# Analog_Signal_Conditioner_V2.net
KiCad netlist of a schematic drawn in Altium Designer
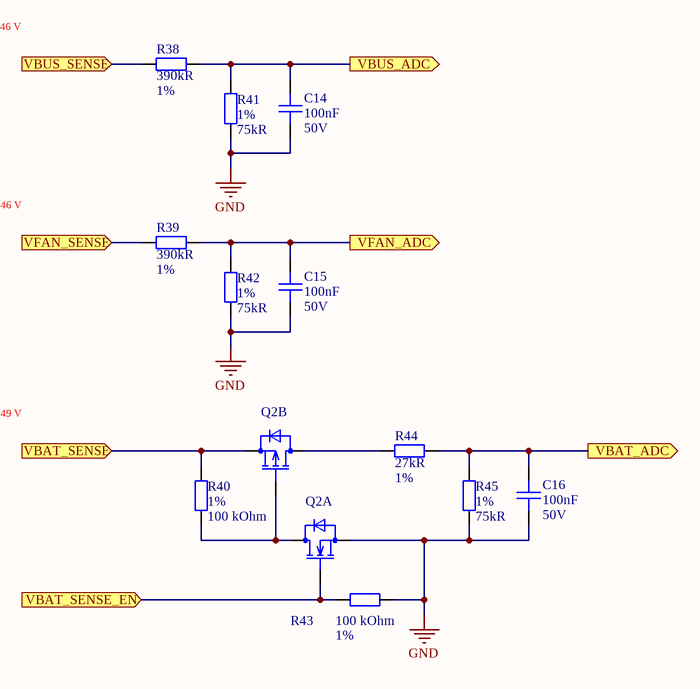
[diagram p0: Analog_Signal_Conditioner_V2.SchDoc]

(export (version "E")
  (design (tool "Eeschema 10.0.6"))
  (components
    (comp (ref "C14")
      (value "CAP CER 0.1UF 50V X7R 0402")
      (footprint "C0402")
      (description "0.1µF ±10% 50V Ceramic Capacitor X7R 0402 (1005 Metric)")
      (fields
        (field (name "MANUFACTURER PART NUMBER") "CGA2B3X7R1H104K050BB")
        (field (name "MANUFACTURER") "TDK")
        (field (name "CAPACITANCE") "100nF")
        (field (name "VOLTAGE") "50V")
      )
      (libsource (lib "capacitors_smd") (part "CAP CER 0.1UF 50V X7R 0402"))
    )
    (comp (ref "C15")
      (value "CAP CER 0.1UF 50V X7R 0402")
      (footprint "C0402")
      (description "0.1µF ±10% 50V Ceramic Capacitor X7R 0402 (1005 Metric)")
      (fields
        (field (name "MANUFACTURER PART NUMBER") "CGA2B3X7R1H104K050BB")
        (field (name "MANUFACTURER") "TDK")
        (field (name "CAPACITANCE") "100nF")
        (field (name "VOLTAGE") "50V")
      )
      (libsource (lib "capacitors_smd") (part "CAP CER 0.1UF 50V X7R 0402"))
    )
    (comp (ref "C16")
      (value "CAP CER 0.1UF 50V X7R 0402")
      (footprint "C0402")
      (description "0.1µF ±10% 50V Ceramic Capacitor X7R 0402 (1005 Metric)")
      (fields
        (field (name "MANUFACTURER PART NUMBER") "CGA2B3X7R1H104K050BB")
        (field (name "MANUFACTURER") "TDK")
        (field (name "CAPACITANCE") "100nF")
        (field (name "VOLTAGE") "50V")
      )
      (libsource (lib "capacitors_smd") (part "CAP CER 0.1UF 50V X7R 0402"))
    )
    (comp (ref "Q2")
      (value "EM6M2T2R")
      (footprint "SON_400UV-7_DIO")
      (description "Mosfet Array N and P-Channel 20V 200mA 150mW Surface Mount EMT6")
      (fields (field (name "MANUFACTURER") "Rohm"))
      (libsource (lib "mosfets") (part "ARRAY MOSFET N/P-CH 20V 0.2A EMT6"))
    )
    (comp (ref "R38")
      (value "RES SMD 390K OHM 1% 1/16W 0402")
      (footprint "R0402")
      (description "390 kOhms ±1% 0.063W, 1/16W Chip Resistor 0402 (1005 Metric) Moisture Resistant Thick Film")
      (fields
        (field (name "MANUFACTURER") "Yageo")
        (field (name "MANUFACTURER PART NUMBER") "RC0402FR-07390KL")
        (field (name "RESISTANCE") "390kR")
        (field (name "TOLERANCE") "1%")
      )
      (libsource (lib "resistors_smd") (part "RES SMD 390K OHM 1% 1/16W 0402"))
    )
    (comp (ref "R39")
      (value "RES SMD 390K OHM 1% 1/16W 0402")
      (footprint "R0402")
      (description "390 kOhms ±1% 0.063W, 1/16W Chip Resistor 0402 (1005 Metric) Moisture Resistant Thick Film")
      (fields
        (field (name "MANUFACTURER") "Yageo")
        (field (name "MANUFACTURER PART NUMBER") "RC0402FR-07390KL")
        (field (name "RESISTANCE") "390kR")
        (field (name "TOLERANCE") "1%")
      )
      (libsource (lib "resistors_smd") (part "RES SMD 390K OHM 1% 1/16W 0402"))
    )
    (comp (ref "R40")
      (value "RES SMD 100K OHM 1% 1/16W 0402")
      (footprint "R0402")
      (description "100 kOhms ±1% 0.063W, 1/16W Chip Resistor 0402 (1005 Metric) Moisture Resistant Thick Film")
      (fields
        (field (name "MANUFACTURER") "Yageo")
        (field (name "MANUFACTURER PART NUMBER") "RC0402FR-07100KL")
        (field (name "TOLERANCE") "1%")
        (field (name "RESISTANCE") "100 kOhm")
      )
      (libsource (lib "") (part "RES SMD 100K OHM 1% 1/16W 0402_1"))
    )
    (comp (ref "R41")
      (value "RES SMD 75K OHM 1% 1/16W 0402")
      (footprint "R0402")
      (description "75 kOhms ±1% 0.063W, 1/16W Chip Resistor 0402 (1005 Metric) Automotive AEC-Q200 Thick Film")
      (fields
        (field (name "MANUFACTURER") "Stackpole Electronics")
        (field (name "MANUFACTURER PART NUMBER") "RMCF0402FT75K0")
        (field (name "TOLERANCE") "1%")
        (field (name "RESISTANCE") "75kR")
      )
      (libsource (lib "resistors_smd") (part "RES SMD 75K OHM 1% 1/16W 0402"))
    )
    (comp (ref "R42")
      (value "RES SMD 75K OHM 1% 1/16W 0402")
      (footprint "R0402")
      (description "75 kOhms ±1% 0.063W, 1/16W Chip Resistor 0402 (1005 Metric) Automotive AEC-Q200 Thick Film")
      (fields
        (field (name "MANUFACTURER") "Stackpole Electronics")
        (field (name "MANUFACTURER PART NUMBER") "RMCF0402FT75K0")
        (field (name "TOLERANCE") "1%")
        (field (name "RESISTANCE") "75kR")
      )
      (libsource (lib "resistors_smd") (part "RES SMD 75K OHM 1% 1/16W 0402"))
    )
    (comp (ref "R43")
      (value "RES SMD 100K OHM 1% 1/16W 0402")
      (footprint "R0402")
      (description "100 kOhms ±1% 0.063W, 1/16W Chip Resistor 0402 (1005 Metric) Moisture Resistant Thick Film")
      (fields
        (field (name "MANUFACTURER") "Yageo")
        (field (name "MANUFACTURER PART NUMBER") "RC0402FR-07100KL")
        (field (name "TOLERANCE") "1%")
        (field (name "RESISTANCE") "100 kOhm")
      )
      (libsource (lib "resistors_smd") (part "RES SMD 100K OHM 1% 1/16W 0402"))
    )
    (comp (ref "R44")
      (value "RES SMD 27K OHM 1% 1/16W 0402")
      (footprint "R0402")
      (description "27 kOhms ±1% 0.063W, 1/16W Chip Resistor 0402 (1005 Metric) Moisture Resistant Thick Film")
      (fields
        (field (name "MANUFACTURER") "Yageo")
        (field (name "MANUFACTURER PART NUMBER") "RC0402FR-0727KL")
        (field (name "RESISTANCE") "27kR")
        (field (name "TOLERANCE") "1%")
      )
      (libsource (lib "resistors_smd") (part "RES SMD 27K OHM 1% 1/16W 0402"))
    )
    (comp (ref "R45")
      (value "RES SMD 75K OHM 1% 1/16W 0402")
      (footprint "R0402")
      (description "75 kOhms ±1% 0.063W, 1/16W Chip Resistor 0402 (1005 Metric) Automotive AEC-Q200 Thick Film")
      (fields
        (field (name "MANUFACTURER") "Stackpole Electronics")
        (field (name "MANUFACTURER PART NUMBER") "RMCF0402FT75K0")
        (field (name "TOLERANCE") "1%")
        (field (name "RESISTANCE") "75kR")
      )
      (libsource (lib "resistors_smd") (part "RES SMD 75K OHM 1% 1/16W 0402"))
    )
  )
  (nets
    (net (code "1") (name "/VBAT_ADC") (class "Default")
      (node (ref "C16") (pin "2") (pinfunction "2_2") (pintype "passive"))
      (node (ref "R44") (pin "2") (pinfunction "2_2") (pintype "passive"))
      (node (ref "R45") (pin "2") (pinfunction "2_2") (pintype "passive"))
    )
    (net (code "2") (name "/VBAT_SENSE") (class "Default")
      (node (ref "Q2") (pin "4") (pinfunction "S_4") (pintype "passive"))
      (node (ref "R40") (pin "2") (pinfunction "2_2") (pintype "passive"))
    )
    (net (code "3") (name "/VBAT_SENSE_EN") (class "Default")
      (node (ref "Q2") (pin "2") (pinfunction "G_2") (pintype "passive"))
      (node (ref "R43") (pin "2") (pinfunction "2_2") (pintype "passive"))
    )
    (net (code "4") (name "/VBUS_ADC") (class "Default")
      (node (ref "C14") (pin "2") (pinfunction "2_2") (pintype "passive"))
      (node (ref "R38") (pin "2") (pinfunction "2_2") (pintype "passive"))
      (node (ref "R41") (pin "2") (pinfunction "2_2") (pintype "passive"))
    )
    (net (code "5") (name "/VBUS_SENSE") (class "Default")
      (node (ref "R38") (pin "1") (pinfunction "1_1") (pintype "passive"))
    )
    (net (code "6") (name "/VFAN_ADC") (class "Default")
      (node (ref "C15") (pin "2") (pinfunction "2_2") (pintype "passive"))
      (node (ref "R39") (pin "2") (pinfunction "2_2") (pintype "passive"))
      (node (ref "R42") (pin "2") (pinfunction "2_2") (pintype "passive"))
    )
    (net (code "7") (name "/VFAN_SENSE") (class "Default")
      (node (ref "R39") (pin "1") (pinfunction "1_1") (pintype "passive"))
    )
    (net (code "8") (name "GND") (class "Default")
      (node (ref "C14") (pin "1") (pinfunction "1_1") (pintype "passive"))
      (node (ref "C15") (pin "1") (pinfunction "1_1") (pintype "passive"))
      (node (ref "C16") (pin "1") (pinfunction "1_1") (pintype "passive"))
      (node (ref "Q2") (pin "1") (pinfunction "S_1") (pintype "passive"))
      (node (ref "R41") (pin "1") (pinfunction "1_1") (pintype "passive"))
      (node (ref "R42") (pin "1") (pinfunction "1_1") (pintype "passive"))
      (node (ref "R43") (pin "1") (pinfunction "1_1") (pintype "passive"))
      (node (ref "R45") (pin "1") (pinfunction "1_1") (pintype "passive"))
    )
    (net (code "9") (name "Net-(Q2A-D)") (class "Default")
      (node (ref "Q2") (pin "5") (pinfunction "G_5") (pintype "passive"))
      (node (ref "Q2") (pin "6") (pinfunction "D_6") (pintype "passive"))
      (node (ref "R40") (pin "1") (pinfunction "1_1") (pintype "passive"))
    )
    (net (code "10") (name "Net-(Q2B-D)") (class "Default")
      (node (ref "Q2") (pin "3") (pinfunction "D_3") (pintype "passive"))
      (node (ref "R44") (pin "1") (pinfunction "1_1") (pintype "passive"))
    )
  )
)
